# 25mW_VTX.net
KiCad netlist of a schematic drawn in Altium Designer
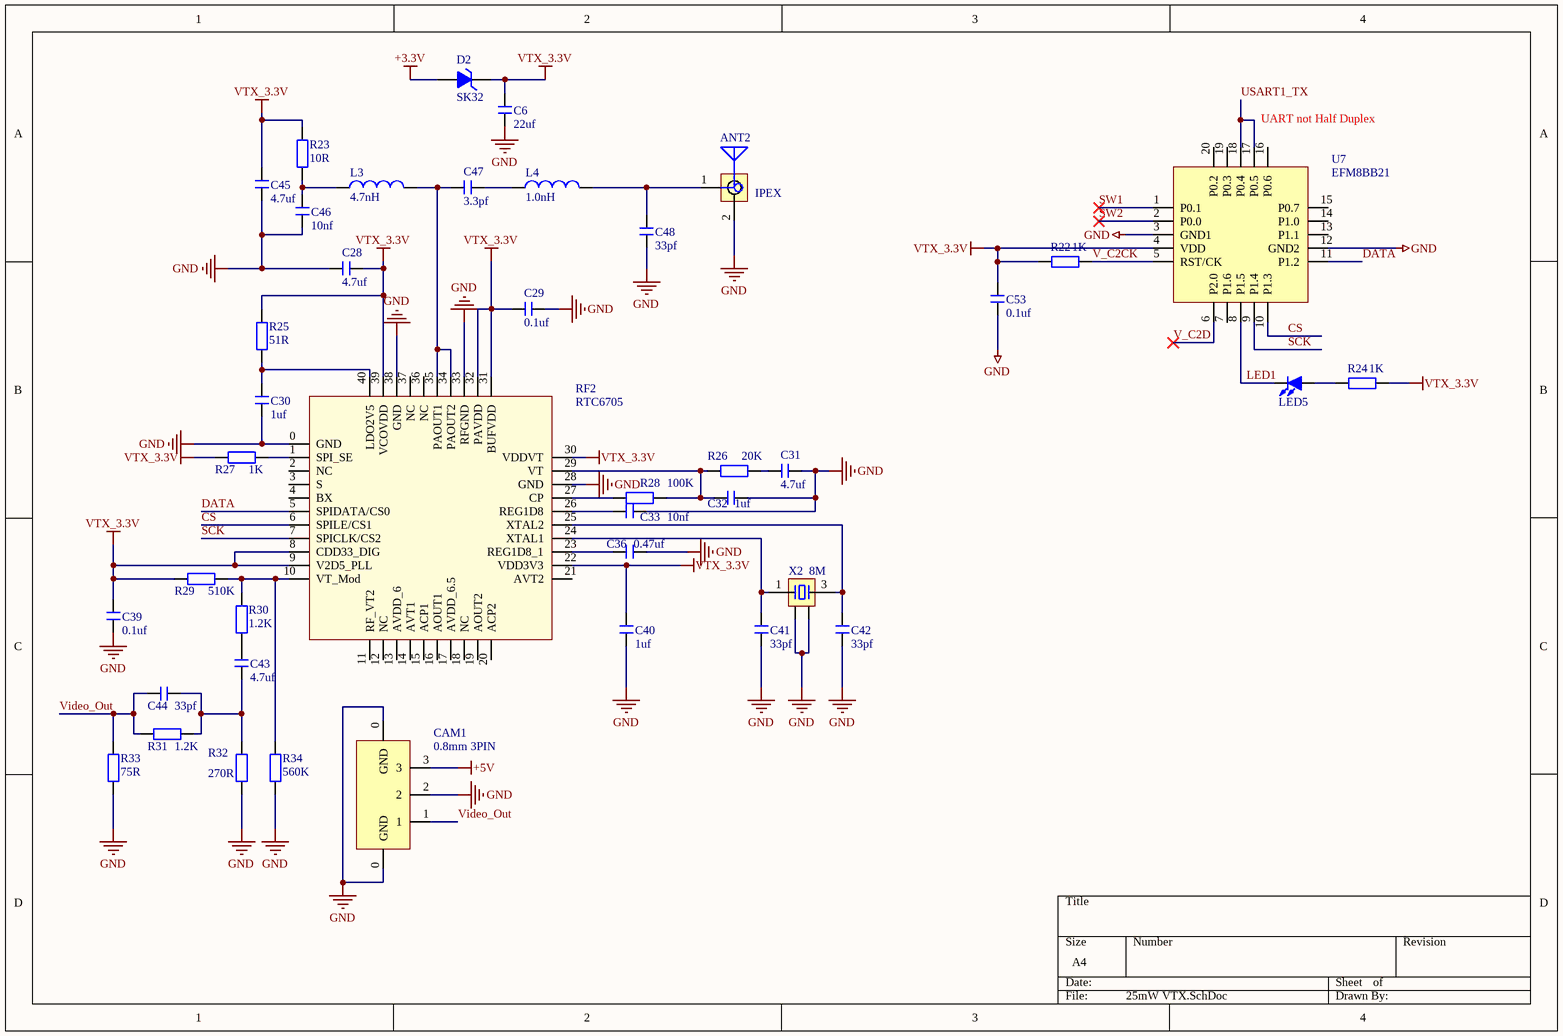
[diagram p0: 25mW VTX.SchDoc]

(export (version "E")
  (design (tool "Eeschema 10.0.6"))
  (components
    (comp (ref "ANT2") (value "IPEX") (footprint "L - IPEX") (libsource (lib "L-RFIC") (part "IPEX")))
    (comp (ref "C6") (value "22uf") (footprint "0402-C-S-1.33*0.5") (libsource (lib "L-电阻电容电感") (part "C")))
    (comp (ref "C28") (value "4.7uf") (footprint "0402-C-S-1.33*0.5") (libsource (lib "L-电阻电容电感") (part "C")))
    (comp (ref "C29") (value "0.1uf") (footprint "0402-C-S-1.33*0.5") (libsource (lib "L-电阻电容电感") (part "C")))
    (comp (ref "C30") (value "1uf") (footprint "0402-C-S-1.33*0.5") (libsource (lib "L-电阻电容电感") (part "C")))
    (comp (ref "C31") (value "4.7uf") (footprint "0402-C-S-1.33*0.5") (libsource (lib "L-电阻电容电感") (part "C")))
    (comp (ref "C32") (value "1uf") (footprint "0402-C-S-1.33*0.5") (libsource (lib "L-电阻电容电感") (part "C")))
    (comp (ref "C33") (value "10nf") (footprint "0402-C-S-1.33*0.5") (libsource (lib "L-电阻电容电感") (part "C")))
    (comp (ref "C36")
      (value "0.47uf")
      (footprint "0402-C-S-1.33*0.5")
      (libsource (lib "L-电阻电容电感") (part "C"))
    )
    (comp (ref "C39") (value "0.1uf") (footprint "0402-C-S-1.33*0.5") (libsource (lib "L-电阻电容电感") (part "C")))
    (comp (ref "C40") (value "1uf") (footprint "0402-C-S-1.33*0.5") (libsource (lib "L-电阻电容电感") (part "C")))
    (comp (ref "C41") (value "33pf") (footprint "0402-C-S-1.33*0.5") (libsource (lib "L-电阻电容电感") (part "C")))
    (comp (ref "C42") (value "33pf") (footprint "0402-C-S-1.33*0.5") (libsource (lib "L-电阻电容电感") (part "C")))
    (comp (ref "C43") (value "4.7uf") (footprint "0402-C-S-1.33*0.5") (libsource (lib "L-电阻电容电感") (part "C")))
    (comp (ref "C44") (value "33pf") (footprint "0402-C-S-1.33*0.5") (libsource (lib "L-电阻电容电感") (part "C")))
    (comp (ref "C45") (value "4.7uf") (footprint "0402-C-S-1.33*0.5") (libsource (lib "L-电阻电容电感") (part "C")))
    (comp (ref "C46") (value "10nf") (footprint "0402-C-S-1.33*0.5") (libsource (lib "L-电阻电容电感") (part "C")))
    (comp (ref "C47") (value "3.3pf") (footprint "0402-C-S-1.33*0.5") (libsource (lib "L-电阻电容电感") (part "C")))
    (comp (ref "C48") (value "33pf") (footprint "0402-C-S-1.33*0.5") (libsource (lib "L-电阻电容电感") (part "C")))
    (comp (ref "C53") (value "0.1uf") (footprint "0402-C-S-1.33*0.5") (libsource (lib "L-电阻电容电感") (part "C")))
    (comp (ref "CAM1")
      (value "0.8mm 3PIN")
      (footprint "X-端子:PCBComponent_1")
      (libsource (lib "X-端子") (part "Component_1"))
    )
    (comp (ref "D2") (value "SK32") (footprint "SOD-123") (libsource (lib "L-二极管、稳压管") (part "1N4148WT")))
    (comp (ref "L3") (value "4.7nH") (footprint "0402-L-1.6*0.5") (libsource (lib "L-电阻电容电感") (part "L")))
    (comp (ref "L4") (value "1.0nH") (footprint "0402-L-1.6*0.5") (libsource (lib "L-电阻电容电感") (part "L")))
    (comp (ref "LED5") (value "LED") (footprint "L-LED 0603B") (libsource (lib "L-LED") (part "LED-2PIN")))
    (comp (ref "R22") (value "1K") (footprint "0402-R-1.38*0.5") (libsource (lib "L-电阻电容电感") (part "R")))
    (comp (ref "R23") (value "10R") (footprint "0402-R-1.38*0.5") (libsource (lib "L-电阻电容电感") (part "R")))
    (comp (ref "R24") (value "1K") (footprint "0402-R-1.38*0.5") (libsource (lib "L-电阻电容电感") (part "R")))
    (comp (ref "R25") (value "51R") (footprint "0402-R-1.38*0.5") (libsource (lib "L-电阻电容电感") (part "R")))
    (comp (ref "R26") (value "20K") (footprint "0402-R-1.38*0.5") (libsource (lib "L-电阻电容电感") (part "R")))
    (comp (ref "R27") (value "1K") (footprint "0402-R-1.38*0.5") (libsource (lib "L-电阻电容电感") (part "R")))
    (comp (ref "R28") (value "100K") (footprint "0402-R-1.38*0.5") (libsource (lib "L-电阻电容电感") (part "R")))
    (comp (ref "R29") (value "510K") (footprint "0402-R-1.38*0.5") (libsource (lib "L-电阻电容电感") (part "R")))
    (comp (ref "R30") (value "1.2K") (footprint "0402-R-1.38*0.5") (libsource (lib "L-电阻电容电感") (part "R")))
    (comp (ref "R31") (value "1.2K") (footprint "0402-R-1.38*0.5") (libsource (lib "L-电阻电容电感") (part "R")))
    (comp (ref "R32") (value "270R") (footprint "0402-R-1.38*0.5") (libsource (lib "L-电阻电容电感") (part "R")))
    (comp (ref "R33") (value "75R") (footprint "0402-R-1.38*0.5") (libsource (lib "L-电阻电容电感") (part "R")))
    (comp (ref "R34") (value "560K") (footprint "0402-R-1.38*0.5") (libsource (lib "L-电阻电容电感") (part "R")))
    (comp (ref "RF2")
      (value "RTC6705")
      (footprint "L - QFN40 6*6")
      (libsource (lib "L-RFIC") (part "RTC6705"))
    )
    (comp (ref "U7") (value "EFM8BB21") (footprint "L - QFN20") (libsource (lib "L-8位单片机") (part "EFM8BB21")))
    (comp (ref "X2")
      (value "8M")
      (footprint "OSC 3225-4P")
      (description "4脚无源晶振")
      (fields (field (name "版权归属") "源创客"))
      (libsource (lib "10.1 - 保险丝-晶振") (part "XTAL-4P"))
    )
  )
  (nets
    (net (code "1") (name "+3.3V") (class "Default")
      (node (ref "D2") (pin "1") (pinfunction "1_1") (pintype "passive"))
    )
    (net (code "2") (name "+5V") (class "Default")
      (node (ref "CAM1") (pin "3") (pinfunction "3_3") (pintype "passive"))
    )
    (net (code "3") (name "/CS") (class "Default")
      (node (ref "RF2") (pin "6") (pinfunction "SPILE/CS1_6") (pintype "passive"))
      (node (ref "U7") (pin "10") (pinfunction "P1.3_10") (pintype "passive"))
    )
    (net (code "4") (name "/DATA") (class "Default")
      (node (ref "RF2") (pin "5") (pinfunction "SPIDATA/CS0_5") (pintype "passive"))
      (node (ref "U7") (pin "11") (pinfunction "P1.2_11") (pintype "passive"))
    )
    (net (code "5") (name "/LED1") (class "Default")
      (node (ref "LED5") (pin "2") (pinfunction "K_2") (pintype "passive"))
      (node (ref "U7") (pin "8") (pinfunction "P1.5_8") (pintype "passive"))
    )
    (net (code "6") (name "/SCK") (class "Default")
      (node (ref "RF2") (pin "7") (pinfunction "SPICLK/CS2_7") (pintype "passive"))
      (node (ref "U7") (pin "9") (pinfunction "P1.4_9") (pintype "passive"))
    )
    (net (code "7") (name "/SW1") (class "Default")
      (node (ref "U7") (pin "1") (pinfunction "P0.1_1") (pintype "passive+no_connect"))
    )
    (net (code "8") (name "/SW2") (class "Default")
      (node (ref "U7") (pin "2") (pinfunction "P0.0_2") (pintype "passive+no_connect"))
    )
    (net (code "9") (name "/USART1_TX") (class "Default")
      (node (ref "U7") (pin "17") (pinfunction "P0.5_17") (pintype "passive"))
      (node (ref "U7") (pin "18") (pinfunction "P0.4_18") (pintype "passive"))
    )
    (net (code "10") (name "/V_C2CK") (class "Default")
      (node (ref "R22") (pin "1") (pinfunction "1_1") (pintype "passive"))
      (node (ref "U7") (pin "5") (pinfunction "RST/CK_5") (pintype "passive"))
    )
    (net (code "11") (name "/V_C2D") (class "Default")
      (node (ref "U7") (pin "6") (pinfunction "P2.0_6") (pintype "passive+no_connect"))
    )
    (net (code "12") (name "/Video_Out") (class "Default")
      (node (ref "C44") (pin "2") (pinfunction "2_2") (pintype "passive"))
      (node (ref "CAM1") (pin "1") (pinfunction "1_1") (pintype "passive"))
      (node (ref "R31") (pin "2") (pinfunction "2_2") (pintype "passive"))
      (node (ref "R33") (pin "2") (pinfunction "2_2") (pintype "passive"))
    )
    (net (code "13") (name "GND") (class "Default")
      (node (ref "ANT2") (pin "2") (pinfunction "GND_2") (pintype "passive"))
      (node (ref "C28") (pin "2") (pinfunction "2_2") (pintype "passive"))
      (node (ref "C29") (pin "1") (pinfunction "1_1") (pintype "passive"))
      (node (ref "C30") (pin "1") (pinfunction "1_1") (pintype "passive"))
      (node (ref "C31") (pin "1") (pinfunction "1_1") (pintype "passive"))
      (node (ref "C32") (pin "2") (pinfunction "2_2") (pintype "passive"))
      (node (ref "C33") (pin "2") (pinfunction "2_2") (pintype "passive"))
      (node (ref "C36") (pin "1") (pinfunction "1_1") (pintype "passive"))
      (node (ref "C39") (pin "2") (pinfunction "2_2") (pintype "passive"))
      (node (ref "C40") (pin "1") (pinfunction "1_1") (pintype "passive"))
      (node (ref "C41") (pin "1") (pinfunction "1_1") (pintype "passive"))
      (node (ref "C42") (pin "1") (pinfunction "1_1") (pintype "passive"))
      (node (ref "C45") (pin "2") (pinfunction "2_2") (pintype "passive"))
      (node (ref "C46") (pin "2") (pinfunction "2_2") (pintype "passive"))
      (node (ref "C48") (pin "2") (pinfunction "2_2") (pintype "passive"))
      (node (ref "C53") (pin "1") (pinfunction "1_1") (pintype "passive"))
      (node (ref "C6") (pin "2") (pinfunction "2_2") (pintype "passive"))
      (node (ref "CAM1") (pin "0") (pinfunction "GND_0") (pintype "passive"))
      (node (ref "CAM1") (pin "2") (pinfunction "2_2") (pintype "passive"))
      (node (ref "R32") (pin "1") (pinfunction "1_1") (pintype "passive"))
      (node (ref "R33") (pin "1") (pinfunction "1_1") (pintype "passive"))
      (node (ref "R34") (pin "1") (pinfunction "1_1") (pintype "passive"))
      (node (ref "RF2") (pin "0") (pinfunction "GND_0") (pintype "passive"))
      (node (ref "RF2") (pin "28") (pinfunction "GND_28") (pintype "passive"))
      (node (ref "RF2") (pin "33") (pinfunction "RFGND_33") (pintype "passive"))
      (node (ref "RF2") (pin "38") (pinfunction "GND_38") (pintype "passive"))
      (node (ref "U7") (pin "12") (pinfunction "GND2_12") (pintype "passive"))
      (node (ref "U7") (pin "3") (pinfunction "GND1_3") (pintype "passive"))
      (node (ref "X2") (pin "2") (pinfunction "2_2") (pintype "passive"))
      (node (ref "X2") (pin "4") (pinfunction "4_4") (pintype "passive"))
    )
    (net (code "14") (name "Net-(ANT2-ANT)") (class "Default")
      (node (ref "ANT2") (pin "1") (pinfunction "ANT_1") (pintype "passive"))
      (node (ref "C48") (pin "1") (pinfunction "1_1") (pintype "passive"))
      (node (ref "L4") (pin "2") (pinfunction "2_2") (pintype "passive"))
    )
    (net (code "15") (name "Net-(C31-Pad2)") (class "Default")
      (node (ref "C31") (pin "2") (pinfunction "2_2") (pintype "passive"))
      (node (ref "R26") (pin "1") (pinfunction "1_1") (pintype "passive"))
    )
    (net (code "16") (name "Net-(C43-Pad1)") (class "Default")
      (node (ref "C43") (pin "1") (pinfunction "1_1") (pintype "passive"))
      (node (ref "C44") (pin "1") (pinfunction "1_1") (pintype "passive"))
      (node (ref "R31") (pin "1") (pinfunction "1_1") (pintype "passive"))
      (node (ref "R32") (pin "2") (pinfunction "2_2") (pintype "passive"))
    )
    (net (code "17") (name "Net-(C43-Pad2)") (class "Default")
      (node (ref "C43") (pin "2") (pinfunction "2_2") (pintype "passive"))
      (node (ref "R30") (pin "1") (pinfunction "1_1") (pintype "passive"))
    )
    (net (code "18") (name "Net-(C46-Pad1)") (class "Default")
      (node (ref "C46") (pin "1") (pinfunction "1_1") (pintype "passive"))
      (node (ref "L3") (pin "1") (pinfunction "1_1") (pintype "passive"))
      (node (ref "R23") (pin "1") (pinfunction "1_1") (pintype "passive"))
    )
    (net (code "19") (name "Net-(C47-Pad1)") (class "Default")
      (node (ref "C47") (pin "1") (pinfunction "1_1") (pintype "passive"))
      (node (ref "L4") (pin "1") (pinfunction "1_1") (pintype "passive"))
    )
    (net (code "20") (name "Net-(LED5-A)") (class "Default")
      (node (ref "LED5") (pin "1") (pinfunction "A_1") (pintype "passive"))
      (node (ref "R24") (pin "2") (pinfunction "2_2") (pintype "passive"))
    )
    (net (code "21") (name "Net-(RF2-CP)") (class "Default")
      (node (ref "R28") (pin "2") (pinfunction "2_2") (pintype "passive"))
      (node (ref "RF2") (pin "27") (pinfunction "CP_27") (pintype "passive"))
    )
    (net (code "22") (name "Net-(RF2-LDO2V5)") (class "Default")
      (node (ref "C30") (pin "2") (pinfunction "2_2") (pintype "passive"))
      (node (ref "R25") (pin "1") (pinfunction "1_1") (pintype "passive"))
      (node (ref "RF2") (pin "40") (pinfunction "LDO2V5_40") (pintype "passive"))
    )
    (net (code "23") (name "Net-(RF2-PAOUT1)") (class "Default")
      (node (ref "C47") (pin "2") (pinfunction "2_2") (pintype "passive"))
      (node (ref "L3") (pin "2") (pinfunction "2_2") (pintype "passive"))
      (node (ref "RF2") (pin "34") (pinfunction "PAOUT2_34") (pintype "passive"))
      (node (ref "RF2") (pin "35") (pinfunction "PAOUT1_35") (pintype "passive"))
    )
    (net (code "24") (name "Net-(RF2-REG1D8)") (class "Default")
      (node (ref "C33") (pin "1") (pinfunction "1_1") (pintype "passive"))
      (node (ref "RF2") (pin "26") (pinfunction "REG1D8_26") (pintype "passive"))
    )
    (net (code "25") (name "Net-(RF2-REG1D8_1)") (class "Default")
      (node (ref "C36") (pin "2") (pinfunction "2_2") (pintype "passive"))
      (node (ref "RF2") (pin "23") (pinfunction "REG1D8_1_23") (pintype "passive"))
    )
    (net (code "26") (name "Net-(RF2-SPI_SE)") (class "Default")
      (node (ref "R27") (pin "2") (pinfunction "2_2") (pintype "passive"))
      (node (ref "RF2") (pin "1") (pinfunction "SPI_SE_1") (pintype "passive"))
    )
    (net (code "27") (name "Net-(RF2-VT)") (class "Default")
      (node (ref "C32") (pin "1") (pinfunction "1_1") (pintype "passive"))
      (node (ref "R26") (pin "2") (pinfunction "2_2") (pintype "passive"))
      (node (ref "R28") (pin "1") (pinfunction "1_1") (pintype "passive"))
      (node (ref "RF2") (pin "29") (pinfunction "VT_29") (pintype "passive"))
    )
    (net (code "28") (name "Net-(RF2-VT_Mod)") (class "Default")
      (node (ref "R29") (pin "2") (pinfunction "2_2") (pintype "passive"))
      (node (ref "R30") (pin "2") (pinfunction "2_2") (pintype "passive"))
      (node (ref "R34") (pin "2") (pinfunction "2_2") (pintype "passive"))
      (node (ref "RF2") (pin "10") (pinfunction "VT_Mod_10") (pintype "passive"))
    )
    (net (code "29") (name "Net-(RF2-XTAL1)") (class "Default")
      (node (ref "C41") (pin "2") (pinfunction "2_2") (pintype "passive"))
      (node (ref "RF2") (pin "24") (pinfunction "XTAL1_24") (pintype "passive"))
      (node (ref "X2") (pin "1") (pinfunction "1_1") (pintype "passive"))
    )
    (net (code "30") (name "Net-(RF2-XTAL2)") (class "Default")
      (node (ref "C42") (pin "2") (pinfunction "2_2") (pintype "passive"))
      (node (ref "RF2") (pin "25") (pinfunction "XTAL2_25") (pintype "passive"))
      (node (ref "X2") (pin "3") (pinfunction "3_3") (pintype "passive"))
    )
    (net (code "31") (name "VTX_3.3V") (class "Default")
      (node (ref "C28") (pin "1") (pinfunction "1_1") (pintype "passive"))
      (node (ref "C29") (pin "2") (pinfunction "2_2") (pintype "passive"))
      (node (ref "C39") (pin "1") (pinfunction "1_1") (pintype "passive"))
      (node (ref "C40") (pin "2") (pinfunction "2_2") (pintype "passive"))
      (node (ref "C45") (pin "1") (pinfunction "1_1") (pintype "passive"))
      (node (ref "C53") (pin "2") (pinfunction "2_2") (pintype "passive"))
      (node (ref "C6") (pin "1") (pinfunction "1_1") (pintype "passive"))
      (node (ref "D2") (pin "2") (pinfunction "2_2") (pintype "passive"))
      (node (ref "R22") (pin "2") (pinfunction "2_2") (pintype "passive"))
      (node (ref "R23") (pin "2") (pinfunction "2_2") (pintype "passive"))
      (node (ref "R24") (pin "1") (pinfunction "1_1") (pintype "passive"))
      (node (ref "R25") (pin "2") (pinfunction "2_2") (pintype "passive"))
      (node (ref "R27") (pin "1") (pinfunction "1_1") (pintype "passive"))
      (node (ref "R29") (pin "1") (pinfunction "1_1") (pintype "passive"))
      (node (ref "RF2") (pin "22") (pinfunction "VDD3V3_22") (pintype "passive"))
      (node (ref "RF2") (pin "30") (pinfunction "VDDVT_30") (pintype "passive"))
      (node (ref "RF2") (pin "31") (pinfunction "BUFVDD_31") (pintype "passive"))
      (node (ref "RF2") (pin "32") (pinfunction "PAVDD_32") (pintype "passive"))
      (node (ref "RF2") (pin "39") (pinfunction "VCOVDD_39") (pintype "passive"))
      (node (ref "RF2") (pin "8") (pinfunction "CDD33_DIG_8") (pintype "passive"))
      (node (ref "RF2") (pin "9") (pinfunction "V2D5_PLL_9") (pintype "passive"))
      (node (ref "U7") (pin "4") (pinfunction "VDD_4") (pintype "passive"))
    )
    (net (code "32") (name "unconnected-(RF2-ACP1-Pad15)") (class "Default")
      (node (ref "RF2") (pin "15") (pinfunction "ACP1_15") (pintype "passive"))
    )
    (net (code "33") (name "unconnected-(RF2-ACP2-Pad20)") (class "Default")
      (node (ref "RF2") (pin "20") (pinfunction "ACP2_20") (pintype "passive"))
    )
    (net (code "34") (name "unconnected-(RF2-AOUT1-Pad16)") (class "Default")
      (node (ref "RF2") (pin "16") (pinfunction "AOUT1_16") (pintype "passive"))
    )
    (net (code "35") (name "unconnected-(RF2-AOUT2-Pad19)") (class "Default")
      (node (ref "RF2") (pin "19") (pinfunction "AOUT2_19") (pintype "passive"))
    )
    (net (code "36") (name "unconnected-(RF2-AVDD_6-Pad13)") (class "Default")
      (node (ref "RF2") (pin "13") (pinfunction "AVDD_6_13") (pintype "passive"))
    )
    (net (code "37") (name "unconnected-(RF2-AVDD_6.5-Pad17)") (class "Default")
      (node (ref "RF2") (pin "17") (pinfunction "AVDD_6.5_17") (pintype "passive"))
    )
    (net (code "38") (name "unconnected-(RF2-AVT1-Pad14)") (class "Default")
      (node (ref "RF2") (pin "14") (pinfunction "AVT1_14") (pintype "passive"))
    )
    (net (code "39") (name "unconnected-(RF2-AVT2-Pad21)") (class "Default")
      (node (ref "RF2") (pin "21") (pinfunction "AVT2_21") (pintype "passive"))
    )
    (net (code "40") (name "unconnected-(RF2-BX-Pad4)") (class "Default")
      (node (ref "RF2") (pin "4") (pinfunction "BX_4") (pintype "passive"))
    )
    (net (code "41") (name "unconnected-(RF2-NC-Pad2)") (class "Default")
      (node (ref "RF2") (pin "2") (pinfunction "NC_2") (pintype "passive"))
    )
    (net (code "42") (name "unconnected-(RF2-NC-Pad12)") (class "Default")
      (node (ref "RF2") (pin "12") (pinfunction "NC_12") (pintype "passive"))
    )
    (net (code "43") (name "unconnected-(RF2-NC-Pad18)") (class "Default")
      (node (ref "RF2") (pin "18") (pinfunction "NC_18") (pintype "passive"))
    )
    (net (code "44") (name "unconnected-(RF2-NC-Pad36)") (class "Default")
      (node (ref "RF2") (pin "36") (pinfunction "NC_36") (pintype "passive"))
    )
    (net (code "45") (name "unconnected-(RF2-NC-Pad37)") (class "Default")
      (node (ref "RF2") (pin "37") (pinfunction "NC_37") (pintype "passive"))
    )
    (net (code "46") (name "unconnected-(RF2-RF_VT2-Pad11)") (class "Default")
      (node (ref "RF2") (pin "11") (pinfunction "RF_VT2_11") (pintype "passive"))
    )
    (net (code "47") (name "unconnected-(RF2-S-Pad3)") (class "Default")
      (node (ref "RF2") (pin "3") (pinfunction "S_3") (pintype "passive"))
    )
    (net (code "48") (name "unconnected-(U7-P0.2-Pad20)") (class "Default")
      (node (ref "U7") (pin "20") (pinfunction "P0.2_20") (pintype "passive"))
    )
    (net (code "49") (name "unconnected-(U7-P0.3-Pad19)") (class "Default")
      (node (ref "U7") (pin "19") (pinfunction "P0.3_19") (pintype "passive"))
    )
    (net (code "50") (name "unconnected-(U7-P0.6-Pad16)") (class "Default")
      (node (ref "U7") (pin "16") (pinfunction "P0.6_16") (pintype "passive"))
    )
    (net (code "51") (name "unconnected-(U7-P0.7-Pad15)") (class "Default")
      (node (ref "U7") (pin "15") (pinfunction "P0.7_15") (pintype "passive"))
    )
    (net (code "52") (name "unconnected-(U7-P1.0-Pad14)") (class "Default")
      (node (ref "U7") (pin "14") (pinfunction "P1.0_14") (pintype "passive"))
    )
    (net (code "53") (name "unconnected-(U7-P1.1-Pad13)") (class "Default")
      (node (ref "U7") (pin "13") (pinfunction "P1.1_13") (pintype "passive"))
    )
    (net (code "54") (name "unconnected-(U7-P1.6-Pad7)") (class "Default")
      (node (ref "U7") (pin "7") (pinfunction "P1.6_7") (pintype "passive"))
    )
  )
)
